# UsbToUart.net
KiCad netlist of a schematic drawn in Altium Designer
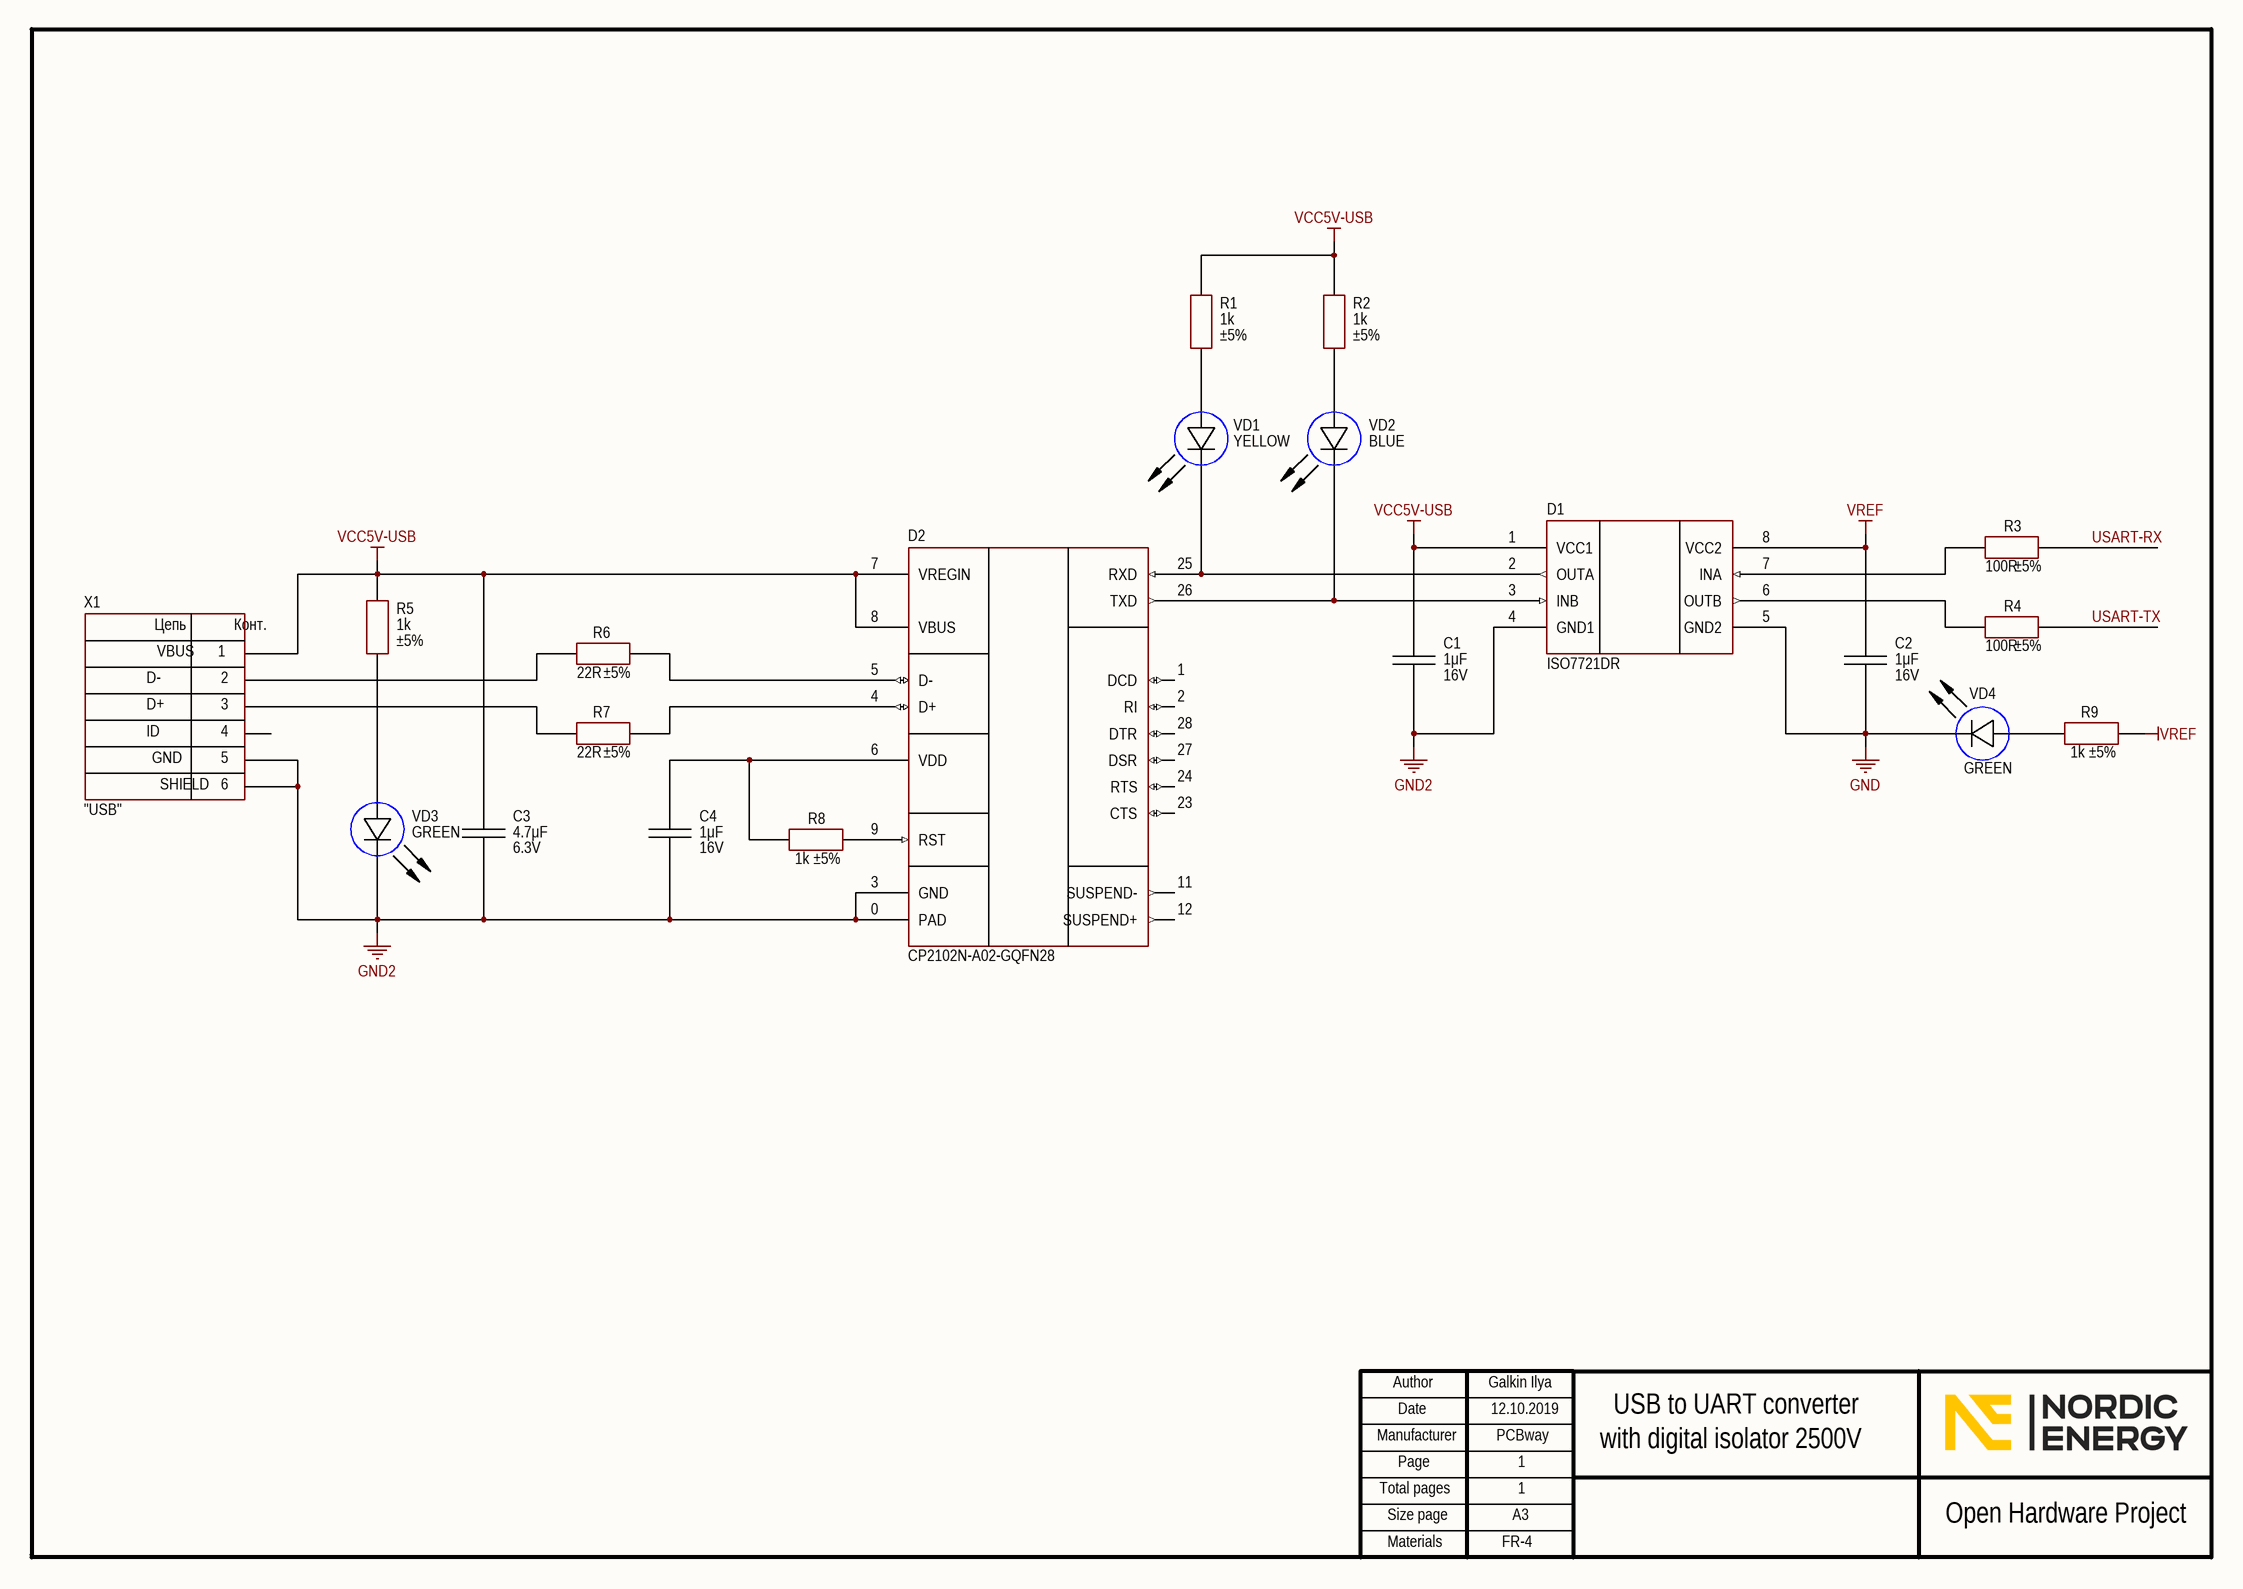
[diagram p0: UsbToUart.SchDoc]

(export (version "E")
  (design (tool "Eeschema 10.0.6"))
  (components
    (comp (ref "C1")
      (value "1μF")
      (footprint "CAP: 0603")
      (fields
        (field (name "MANUFACTURER") "Samsung")
        (field (name "PARTNUMBER") "CL10B105KO8NNNC")
        (field (name "VALUEMANUFACTURERPARTNUMBER") "Ceramic capacitor, 1μF, X7R, ±10%, 16V, 0603, -55...+125°C")
        (field (name "VOLTAGE") "16V")
      )
      (libsource (lib "Capacitor") (part "Ceramic_0603"))
    )
    (comp (ref "C2")
      (value "1μF")
      (footprint "CAP: 0603")
      (fields
        (field (name "MANUFACTURER") "Samsung")
        (field (name "PARTNUMBER") "CL10B105KO8NNNC")
        (field (name "VALUEMANUFACTURERPARTNUMBER") "Ceramic capacitor, 1μF, X7R, ±10%, 16V, 0603, -55...+125°C")
        (field (name "VOLTAGE") "16V")
      )
      (libsource (lib "Capacitor") (part "Ceramic_0603"))
    )
    (comp (ref "C3")
      (value "4.7μF")
      (footprint "CAP: 0603")
      (fields
        (field (name "MANUFACTURER") "Samsung")
        (field (name "PARTNUMBER") "CL10B475KQ8NQNC")
        (field (name "VALUEMANUFACTURERPARTNUMBER") "Ceramic capacitor, 4.7μF, X7R, ±10%, 6.3V, 0603, -55...+125°C")
        (field (name "VOLTAGE") "6.3V")
      )
      (libsource (lib "Capacitor") (part "Ceramic_0603"))
    )
    (comp (ref "C4")
      (value "1μF")
      (footprint "CAP: 0603")
      (fields
        (field (name "MANUFACTURER") "Samsung")
        (field (name "PARTNUMBER") "CL10B105KO8NNNC")
        (field (name "VALUEMANUFACTURERPARTNUMBER") "Ceramic capacitor, 1μF, X7R, ±10%, 16V, 0603, -55...+125°C")
        (field (name "VOLTAGE") "16V")
      )
      (libsource (lib "Capacitor") (part "Ceramic_0603"))
    )
    (comp (ref "D1")
      (value "~")
      (footprint "8-SOIC")
      (description "Digital isolator")
      (fields
        (field (name "MANUFACTURER") "Texas Instruments")
        (field (name "VALUEMANUFACTURERPARTNUMBER") "IC digital isolator, 100Mbps, 3000Vrms, 2.25...5.5V, -55...+125°C, 8-SOIC")
        (field (name "PARTNUMBER") "ISO7721DR")
      )
      (libsource (lib "IC. Interface") (part "ISO7721DR"))
    )
    (comp (ref "D2")
      (value "~")
      (footprint "28-QFN (5x5)")
      (description "USB-to-UART")
      (fields
        (field (name "MANUFACTURER") "Silicon Labs")
        (field (name "VALUEMANUFACTURERPARTNUMBER") "IC usb-to-uart bridge, USB2.0, 3...3.6V, -40...+85°C, 28-VFQFN")
        (field (name "PARTNUMBER") "CP2102N-A02-GQFN28")
      )
      (libsource (lib "IC. Interface") (part "CP2102N"))
    )
    (comp (ref "R1")
      (value "1k")
      (footprint "RES: 0603")
      (fields
        (field (name "MANUFACTURER") "Yageo")
        (field (name "PARTNUMBER") "RC0603JR-071KL")
        (field (name "VALUEMANUFACTURERPARTNUMBER") "Resistor film, 1k, ±5%, 0603, 0.1W, -55...+125°C")
        (field (name "TOLERANCE") "±5%")
      )
      (libsource (lib "") (part "Resistor_0603_1"))
    )
    (comp (ref "R2")
      (value "1k")
      (footprint "RES: 0603")
      (fields
        (field (name "MANUFACTURER") "Yageo")
        (field (name "PARTNUMBER") "RC0603JR-071KL")
        (field (name "VALUEMANUFACTURERPARTNUMBER") "Resistor film, 1k, ±5%, 0603, 0.1W, -55...+125°C")
        (field (name "TOLERANCE") "±5%")
      )
      (libsource (lib "") (part "Resistor_0603_1"))
    )
    (comp (ref "R3")
      (value "100R")
      (footprint "RES: 0603")
      (fields
        (field (name "MANUFACTURER") "Yageo")
        (field (name "PARTNUMBER") "RC0603JR-07100RL")
        (field (name "VALUEMANUFACTURERPARTNUMBER") "Resistor film, 100R, ±5%, 0603, 0.1W, -55...+125°C")
        (field (name "TOLERANCE") "±5%")
      )
      (libsource (lib "Resistor") (part "Resistor_0603"))
    )
    (comp (ref "R4")
      (value "100R")
      (footprint "RES: 0603")
      (fields
        (field (name "MANUFACTURER") "Yageo")
        (field (name "PARTNUMBER") "RC0603JR-07100RL")
        (field (name "VALUEMANUFACTURERPARTNUMBER") "Resistor film, 100R, ±5%, 0603, 0.1W, -55...+125°C")
        (field (name "TOLERANCE") "±5%")
      )
      (libsource (lib "Resistor") (part "Resistor_0603"))
    )
    (comp (ref "R5")
      (value "1k")
      (footprint "RES: 0603")
      (fields
        (field (name "MANUFACTURER") "Yageo")
        (field (name "PARTNUMBER") "RC0603JR-071KL")
        (field (name "VALUEMANUFACTURERPARTNUMBER") "Resistor film, 1k, ±5%, 0603, 0.1W, -55...+125°C")
        (field (name "TOLERANCE") "±5%")
      )
      (libsource (lib "") (part "Resistor_0603_1"))
    )
    (comp (ref "R6")
      (value "22R")
      (footprint "RES: 0603")
      (fields
        (field (name "MANUFACTURER") "Yageo")
        (field (name "PARTNUMBER") "RC0603JR-0722RL")
        (field (name "VALUEMANUFACTURERPARTNUMBER") "Resistor film, 22R, ±5%, 0603, 0.1W, -55...+125°C")
        (field (name "TOLERANCE") "±5%")
      )
      (libsource (lib "Resistor") (part "Resistor_0603"))
    )
    (comp (ref "R7")
      (value "22R")
      (footprint "RES: 0603")
      (fields
        (field (name "MANUFACTURER") "Yageo")
        (field (name "PARTNUMBER") "RC0603JR-0722RL")
        (field (name "VALUEMANUFACTURERPARTNUMBER") "Resistor film, 22R, ±5%, 0603, 0.1W, -55...+125°C")
        (field (name "TOLERANCE") "±5%")
      )
      (libsource (lib "Resistor") (part "Resistor_0603"))
    )
    (comp (ref "R8")
      (value "1k")
      (footprint "RES: 0603")
      (fields
        (field (name "MANUFACTURER") "Yageo")
        (field (name "PARTNUMBER") "RC0603JR-071KL")
        (field (name "VALUEMANUFACTURERPARTNUMBER") "Resistor film, 1k, ±5%, 0603, 0.1W, -55...+125°C")
        (field (name "TOLERANCE") "±5%")
      )
      (libsource (lib "Resistor") (part "Resistor_0603"))
    )
    (comp (ref "R9")
      (value "1k")
      (footprint "RES: 0603")
      (fields
        (field (name "MANUFACTURER") "Yageo")
        (field (name "PARTNUMBER") "RC0603JR-071KL")
        (field (name "VALUEMANUFACTURERPARTNUMBER") "Resistor film, 1k, ±5%, 0603, 0.1W, -55...+125°C")
        (field (name "TOLERANCE") "±5%")
      )
      (libsource (lib "") (part "Resistor_0603_2"))
    )
    (comp (ref "VD1")
      (value "~")
      (footprint "LED: 0603Y")
      (fields
        (field (name "MANUFACTURER") "Wurth")
        (field (name "VALUEMANUFACTURERPARTNUMBER") "LED, 20mA, 2V, 0603, -55...+150°C")
        (field (name "PARTNUMBER") "150060YS75000")
        (field (name "COLOR") "YELLOW")
      )
      (libsource (lib "Diode") (part "LED_single"))
    )
    (comp (ref "VD2")
      (value "~")
      (footprint "LED: 0603B")
      (fields
        (field (name "MANUFACTURER") "Wurth")
        (field (name "VALUEMANUFACTURERPARTNUMBER") "LED, 20mA, 3.2V, 0603, -55...+150°C")
        (field (name "PARTNUMBER") "150060BS75000")
        (field (name "COLOR") "BLUE")
      )
      (libsource (lib "Diode") (part "LED_single"))
    )
    (comp (ref "VD3")
      (value "~")
      (footprint "LED: 0603G")
      (fields
        (field (name "MANUFACTURER") "Wurth")
        (field (name "VALUEMANUFACTURERPARTNUMBER") "LED, 20mA, 2V, 0603, -55...+150°C")
        (field (name "PARTNUMBER") "150060VS75000")
        (field (name "COLOR") "GREEN")
      )
      (libsource (lib "Diode") (part "LED_single"))
    )
    (comp (ref "VD4")
      (value "~")
      (footprint "LED: 0603G")
      (fields
        (field (name "MANUFACTURER") "Wurth")
        (field (name "VALUEMANUFACTURERPARTNUMBER") "LED, 20mA, 2V, 0603, -55...+150°C")
        (field (name "PARTNUMBER") "150060VS75000")
        (field (name "COLOR") "GREEN")
      )
      (libsource (lib "Diode") (part "LED_single"))
    )
    (comp (ref "X1")
      (value "~")
      (footprint "CON: USB micro-A (ZX62-B-5PA)")
      (fields
        (field (name "MANUFACTURER") "Hirose Electric")
        (field (name "VALUEMANUFACTURERPARTNUMBER") "USB micro B")
        (field (name "PARTNUMBER") "ZX62-B-5PA")
        (field (name "COMMENTTEXT") "\"USB\"")
      )
      (libsource (lib "Connector") (part "Connector_USB_micro_B"))
    )
  )
  (nets
    (net (code "1") (name "/USART-RX") (class "Default")
      (node (ref "R3") (pin "2") (pinfunction "2_2") (pintype "passive"))
    )
    (net (code "2") (name "/USART-TX") (class "Default")
      (node (ref "R4") (pin "2") (pinfunction "2_2") (pintype "passive"))
    )
    (net (code "3") (name "GND") (class "Default")
      (node (ref "C2") (pin "1") (pinfunction "1_1") (pintype "power_in"))
      (node (ref "D1") (pin "5") (pinfunction "GND2_5") (pintype "passive"))
      (node (ref "VD4") (pin "2") (pinfunction "C_2") (pintype "passive"))
    )
    (net (code "4") (name "GND2") (class "Default")
      (node (ref "C1") (pin "1") (pinfunction "1_1") (pintype "power_in"))
      (node (ref "C3") (pin "1") (pinfunction "1_1") (pintype "power_in"))
      (node (ref "C4") (pin "1") (pinfunction "1_1") (pintype "power_in"))
      (node (ref "D1") (pin "4") (pinfunction "GND1_4") (pintype "passive"))
      (node (ref "D2") (pin "0") (pinfunction "PAD_0") (pintype "passive"))
      (node (ref "D2") (pin "3") (pinfunction "GND_3") (pintype "passive"))
      (node (ref "VD3") (pin "2") (pinfunction "C_2") (pintype "passive"))
      (node (ref "X1") (pin "0") (pinfunction "0_0") (pintype "passive"))
      (node (ref "X1") (pin "5") (pinfunction "5_5") (pintype "passive"))
    )
    (net (code "5") (name "Net-(D1-INA)") (class "Default")
      (node (ref "D1") (pin "7") (pinfunction "INA_7") (pintype "input"))
      (node (ref "R3") (pin "1") (pinfunction "1_1") (pintype "passive"))
    )
    (net (code "6") (name "Net-(D1-INB)") (class "Default")
      (node (ref "D1") (pin "3") (pinfunction "INB_3") (pintype "input"))
      (node (ref "D2") (pin "26") (pinfunction "TXD_26") (pintype "output"))
      (node (ref "VD2") (pin "2") (pinfunction "C_2") (pintype "passive"))
    )
    (net (code "7") (name "Net-(D1-OUTA)") (class "Default")
      (node (ref "D1") (pin "2") (pinfunction "OUTA_2") (pintype "output"))
      (node (ref "D2") (pin "25") (pinfunction "RXD_25") (pintype "input"))
      (node (ref "VD1") (pin "2") (pinfunction "C_2") (pintype "passive"))
    )
    (net (code "8") (name "Net-(D1-OUTB)") (class "Default")
      (node (ref "D1") (pin "6") (pinfunction "OUTB_6") (pintype "output"))
      (node (ref "R4") (pin "1") (pinfunction "1_1") (pintype "passive"))
    )
    (net (code "9") (name "Net-(D2-D+)") (class "Default")
      (node (ref "D2") (pin "4") (pinfunction "D+_4") (pintype "bidirectional"))
      (node (ref "R7") (pin "2") (pinfunction "2_2") (pintype "passive"))
    )
    (net (code "10") (name "Net-(D2-D-)") (class "Default")
      (node (ref "D2") (pin "5") (pinfunction "D-_5") (pintype "bidirectional"))
      (node (ref "R6") (pin "2") (pinfunction "2_2") (pintype "passive"))
    )
    (net (code "11") (name "Net-(D2-RST)") (class "Default")
      (node (ref "D2") (pin "9") (pinfunction "RST_9") (pintype "input"))
      (node (ref "R8") (pin "2") (pinfunction "2_2") (pintype "passive"))
    )
    (net (code "12") (name "Net-(D2-VDD)") (class "Default")
      (node (ref "C4") (pin "2") (pinfunction "2_2") (pintype "power_in"))
      (node (ref "D2") (pin "6") (pinfunction "VDD_6") (pintype "passive"))
      (node (ref "R8") (pin "1") (pinfunction "1_1") (pintype "passive"))
    )
    (net (code "13") (name "Net-(R6-Pad1)") (class "Default")
      (node (ref "R6") (pin "1") (pinfunction "1_1") (pintype "passive"))
      (node (ref "X1") (pin "2") (pinfunction "2_2") (pintype "passive"))
    )
    (net (code "14") (name "Net-(R7-Pad1)") (class "Default")
      (node (ref "R7") (pin "1") (pinfunction "1_1") (pintype "passive"))
      (node (ref "X1") (pin "3") (pinfunction "3_3") (pintype "passive"))
    )
    (net (code "15") (name "Net-(VD1-A)") (class "Default")
      (node (ref "R1") (pin "1") (pinfunction "1_1") (pintype "passive"))
      (node (ref "VD1") (pin "1") (pinfunction "A_1") (pintype "passive"))
    )
    (net (code "16") (name "Net-(VD2-A)") (class "Default")
      (node (ref "R2") (pin "1") (pinfunction "1_1") (pintype "passive"))
      (node (ref "VD2") (pin "1") (pinfunction "A_1") (pintype "passive"))
    )
    (net (code "17") (name "Net-(VD3-A)") (class "Default")
      (node (ref "R5") (pin "1") (pinfunction "1_1") (pintype "passive"))
      (node (ref "VD3") (pin "1") (pinfunction "A_1") (pintype "passive"))
    )
    (net (code "18") (name "Net-(VD4-A)") (class "Default")
      (node (ref "R9") (pin "2") (pinfunction "2_2") (pintype "passive"))
      (node (ref "VD4") (pin "1") (pinfunction "A_1") (pintype "passive"))
    )
    (net (code "19") (name "VCC5V-USB") (class "Default")
      (node (ref "C1") (pin "2") (pinfunction "2_2") (pintype "power_in"))
      (node (ref "C3") (pin "2") (pinfunction "2_2") (pintype "power_in"))
      (node (ref "D1") (pin "1") (pinfunction "VCC1_1") (pintype "passive"))
      (node (ref "D2") (pin "7") (pinfunction "VREGIN_7") (pintype "passive"))
      (node (ref "D2") (pin "8") (pinfunction "VBUS_8") (pintype "passive"))
      (node (ref "R1") (pin "2") (pinfunction "2_2") (pintype "passive"))
      (node (ref "R2") (pin "2") (pinfunction "2_2") (pintype "passive"))
      (node (ref "R5") (pin "2") (pinfunction "2_2") (pintype "passive"))
      (node (ref "X1") (pin "1") (pintype "passive"))
    )
    (net (code "20") (name "VREF") (class "Default")
      (node (ref "C2") (pin "2") (pinfunction "2_2") (pintype "power_in"))
      (node (ref "D1") (pin "8") (pinfunction "VCC2_8") (pintype "passive"))
      (node (ref "R9") (pin "1") (pinfunction "1_1") (pintype "passive"))
    )
    (net (code "21") (name "unconnected-(D2-CTS-Pad23)") (class "Default")
      (node (ref "D2") (pin "23") (pinfunction "CTS_23") (pintype "bidirectional"))
    )
    (net (code "22") (name "unconnected-(D2-DCD-Pad1)") (class "Default")
      (node (ref "D2") (pin "1") (pinfunction "DCD_1") (pintype "bidirectional"))
    )
    (net (code "23") (name "unconnected-(D2-DSR-Pad27)") (class "Default")
      (node (ref "D2") (pin "27") (pinfunction "DSR_27") (pintype "bidirectional"))
    )
    (net (code "24") (name "unconnected-(D2-DTR-Pad28)") (class "Default")
      (node (ref "D2") (pin "28") (pinfunction "DTR_28") (pintype "bidirectional"))
    )
    (net (code "25") (name "unconnected-(D2-RI-Pad2)") (class "Default")
      (node (ref "D2") (pin "2") (pinfunction "RI_2") (pintype "bidirectional"))
    )
    (net (code "26") (name "unconnected-(D2-RTS-Pad24)") (class "Default")
      (node (ref "D2") (pin "24") (pinfunction "RTS_24") (pintype "bidirectional"))
    )
    (net (code "27") (name "unconnected-(D2-SUSPEND+-Pad12)") (class "Default")
      (node (ref "D2") (pin "12") (pinfunction "SUSPEND+_12") (pintype "output"))
    )
    (net (code "28") (name "unconnected-(D2-SUSPEND--Pad11)") (class "Default")
      (node (ref "D2") (pin "11") (pinfunction "SUSPEND-_11") (pintype "output"))
    )
    (net (code "29") (name "unconnected-(X1-Pad4)") (class "Default")
      (node (ref "X1") (pin "4") (pinfunction "4_4") (pintype "passive"))
    )
  )
)
